# switch.net
KiCad netlist of a schematic drawn in EAGLE
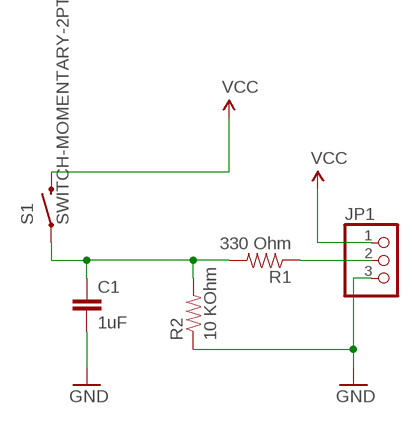
[diagram p0: schematic, sheet 1]

(export (version "E")
  (design (tool "Eeschema 10.0.6"))
  (components
    (comp (ref "C1")
      (value "1uF")
      (footprint "eagle-import:CAP-PTH-5MM")
      (libsource (lib "eagle-import") (part "CAPPTH1"))
    )
    (comp (ref "JP1")
      (value "PINHD-1X3")
      (footprint "eagle-import:1X03")
      (libsource (lib "eagle-import") (part "PINHD-1X3"))
    )
    (comp (ref "R1")
      (value "330 Ohm")
      (footprint "eagle-import:AXIAL-0.4")
      (libsource (lib "eagle-import") (part "RESISTORPTH-1/4W"))
    )
    (comp (ref "R2")
      (value "10 KOhm")
      (footprint "eagle-import:AXIAL-0.4")
      (libsource (lib "eagle-import") (part "RESISTORPTH-1/4W"))
    )
    (comp (ref "S1")
      (value "SWITCH-MOMENTARY-2PTH")
      (footprint "eagle-import:TACTILE-PTH")
      (libsource (lib "eagle-import") (part "SWITCH-MOMENTARY-2PTH"))
    )
  )
  (nets
    (net (code "1") (name "GND") (class "Default")
      (node (ref "C1") (pin "2") (pinfunction "2_2") (pintype "passive"))
      (node (ref "JP1") (pin "3") (pinfunction "3_3") (pintype "passive"))
      (node (ref "R2") (pin "P$1") (pinfunction "1_P$1") (pintype "passive"))
    )
    (net (code "2") (name "Net-(R1-1)") (class "Default")
      (node (ref "JP1") (pin "2") (pinfunction "2_2") (pintype "passive"))
      (node (ref "R1") (pin "P$1") (pinfunction "1_P$1") (pintype "passive"))
    )
    (net (code "3") (name "Net-(R1-2)") (class "Default")
      (node (ref "C1") (pin "1") (pinfunction "1_1") (pintype "passive"))
      (node (ref "R1") (pin "P$2") (pinfunction "2_P$2") (pintype "passive"))
      (node (ref "R2") (pin "P$2") (pinfunction "2_P$2") (pintype "passive"))
      (node (ref "S1") (pin "1") (pinfunction "1_1") (pintype "passive"))
    )
    (net (code "4") (name "VCC") (class "Default")
      (node (ref "JP1") (pin "1") (pinfunction "1_1") (pintype "passive"))
      (node (ref "S1") (pin "4") (pinfunction "2_4") (pintype "passive"))
    )
  )
)
